# 13_LED_Array.net
KiCad netlist of a schematic drawn in Altium Designer
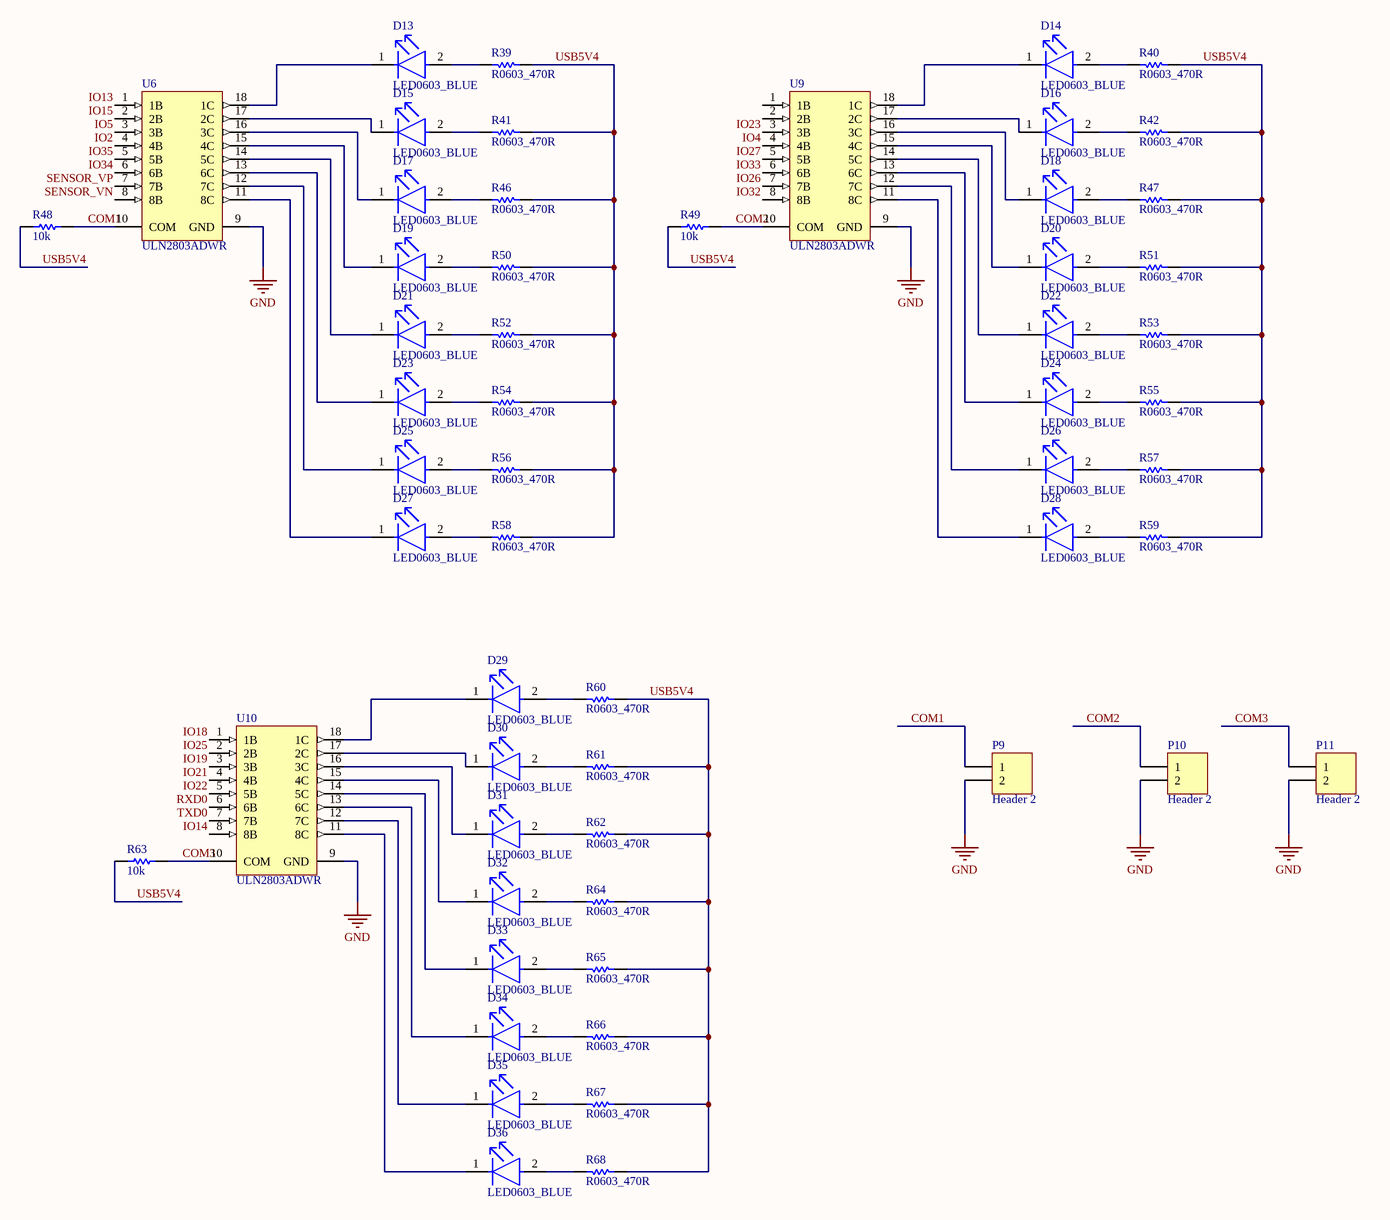
[diagram p0: 13_LED_Array.SchDoc]

(export (version "E")
  (design (tool "Eeschema 10.0.6"))
  (components
    (comp (ref "D13")
      (value "LED0603_BLUE")
      (footprint "FP-LTST-C191TBKT-MFG")
      (description "LED BLUE CLEAR CHIP SMD")
      (libsource (lib "Altium Content Vault") (part "8706943c75ba83719d021d2fdc84c58"))
    )
    (comp (ref "D14")
      (value "LED0603_BLUE")
      (footprint "FP-LTST-C191TBKT-MFG")
      (description "LED BLUE CLEAR CHIP SMD")
      (libsource (lib "Altium Content Vault") (part "8706943c75ba83719d021d2fdc84c58"))
    )
    (comp (ref "D15")
      (value "LED0603_BLUE")
      (footprint "FP-LTST-C191TBKT-MFG")
      (description "LED BLUE CLEAR CHIP SMD")
      (libsource (lib "Altium Content Vault") (part "8706943c75ba83719d021d2fdc84c58"))
    )
    (comp (ref "D16")
      (value "LED0603_BLUE")
      (footprint "FP-LTST-C191TBKT-MFG")
      (description "LED BLUE CLEAR CHIP SMD")
      (libsource (lib "Altium Content Vault") (part "8706943c75ba83719d021d2fdc84c58"))
    )
    (comp (ref "D17")
      (value "LED0603_BLUE")
      (footprint "FP-LTST-C191TBKT-MFG")
      (description "LED BLUE CLEAR CHIP SMD")
      (libsource (lib "Altium Content Vault") (part "8706943c75ba83719d021d2fdc84c58"))
    )
    (comp (ref "D18")
      (value "LED0603_BLUE")
      (footprint "FP-LTST-C191TBKT-MFG")
      (description "LED BLUE CLEAR CHIP SMD")
      (libsource (lib "Altium Content Vault") (part "8706943c75ba83719d021d2fdc84c58"))
    )
    (comp (ref "D19")
      (value "LED0603_BLUE")
      (footprint "FP-LTST-C191TBKT-MFG")
      (description "LED BLUE CLEAR CHIP SMD")
      (libsource (lib "Altium Content Vault") (part "8706943c75ba83719d021d2fdc84c58"))
    )
    (comp (ref "D20")
      (value "LED0603_BLUE")
      (footprint "FP-LTST-C191TBKT-MFG")
      (description "LED BLUE CLEAR CHIP SMD")
      (libsource (lib "Altium Content Vault") (part "8706943c75ba83719d021d2fdc84c58"))
    )
    (comp (ref "D21")
      (value "LED0603_BLUE")
      (footprint "FP-LTST-C191TBKT-MFG")
      (description "LED BLUE CLEAR CHIP SMD")
      (libsource (lib "Altium Content Vault") (part "8706943c75ba83719d021d2fdc84c58"))
    )
    (comp (ref "D22")
      (value "LED0603_BLUE")
      (footprint "FP-LTST-C191TBKT-MFG")
      (description "LED BLUE CLEAR CHIP SMD")
      (libsource (lib "Altium Content Vault") (part "8706943c75ba83719d021d2fdc84c58"))
    )
    (comp (ref "D23")
      (value "LED0603_BLUE")
      (footprint "FP-LTST-C191TBKT-MFG")
      (description "LED BLUE CLEAR CHIP SMD")
      (libsource (lib "Altium Content Vault") (part "8706943c75ba83719d021d2fdc84c58"))
    )
    (comp (ref "D24")
      (value "LED0603_BLUE")
      (footprint "FP-LTST-C191TBKT-MFG")
      (description "LED BLUE CLEAR CHIP SMD")
      (libsource (lib "Altium Content Vault") (part "8706943c75ba83719d021d2fdc84c58"))
    )
    (comp (ref "D25")
      (value "LED0603_BLUE")
      (footprint "FP-LTST-C191TBKT-MFG")
      (description "LED BLUE CLEAR CHIP SMD")
      (libsource (lib "Altium Content Vault") (part "8706943c75ba83719d021d2fdc84c58"))
    )
    (comp (ref "D26")
      (value "LED0603_BLUE")
      (footprint "FP-LTST-C191TBKT-MFG")
      (description "LED BLUE CLEAR CHIP SMD")
      (libsource (lib "Altium Content Vault") (part "8706943c75ba83719d021d2fdc84c58"))
    )
    (comp (ref "D27")
      (value "LED0603_BLUE")
      (footprint "FP-LTST-C191TBKT-MFG")
      (description "LED BLUE CLEAR CHIP SMD")
      (libsource (lib "Altium Content Vault") (part "8706943c75ba83719d021d2fdc84c58"))
    )
    (comp (ref "D28")
      (value "LED0603_BLUE")
      (footprint "FP-LTST-C191TBKT-MFG")
      (description "LED BLUE CLEAR CHIP SMD")
      (libsource (lib "Altium Content Vault") (part "8706943c75ba83719d021d2fdc84c58"))
    )
    (comp (ref "D29")
      (value "LED0603_BLUE")
      (footprint "FP-LTST-C191TBKT-MFG")
      (description "LED BLUE CLEAR CHIP SMD")
      (libsource (lib "Altium Content Vault") (part "8706943c75ba83719d021d2fdc84c58"))
    )
    (comp (ref "D30")
      (value "LED0603_BLUE")
      (footprint "FP-LTST-C191TBKT-MFG")
      (description "LED BLUE CLEAR CHIP SMD")
      (libsource (lib "Altium Content Vault") (part "8706943c75ba83719d021d2fdc84c58"))
    )
    (comp (ref "D31")
      (value "LED0603_BLUE")
      (footprint "FP-LTST-C191TBKT-MFG")
      (description "LED BLUE CLEAR CHIP SMD")
      (libsource (lib "Altium Content Vault") (part "8706943c75ba83719d021d2fdc84c58"))
    )
    (comp (ref "D32")
      (value "LED0603_BLUE")
      (footprint "FP-LTST-C191TBKT-MFG")
      (description "LED BLUE CLEAR CHIP SMD")
      (libsource (lib "Altium Content Vault") (part "8706943c75ba83719d021d2fdc84c58"))
    )
    (comp (ref "D33")
      (value "LED0603_BLUE")
      (footprint "FP-LTST-C191TBKT-MFG")
      (description "LED BLUE CLEAR CHIP SMD")
      (libsource (lib "Altium Content Vault") (part "8706943c75ba83719d021d2fdc84c58"))
    )
    (comp (ref "D34")
      (value "LED0603_BLUE")
      (footprint "FP-LTST-C191TBKT-MFG")
      (description "LED BLUE CLEAR CHIP SMD")
      (libsource (lib "Altium Content Vault") (part "8706943c75ba83719d021d2fdc84c58"))
    )
    (comp (ref "D35")
      (value "LED0603_BLUE")
      (footprint "FP-LTST-C191TBKT-MFG")
      (description "LED BLUE CLEAR CHIP SMD")
      (libsource (lib "Altium Content Vault") (part "8706943c75ba83719d021d2fdc84c58"))
    )
    (comp (ref "D36")
      (value "LED0603_BLUE")
      (footprint "FP-LTST-C191TBKT-MFG")
      (description "LED BLUE CLEAR CHIP SMD")
      (libsource (lib "Altium Content Vault") (part "8706943c75ba83719d021d2fdc84c58"))
    )
    (comp (ref "P9")
      (value "Header 2")
      (footprint "HDR1X2")
      (description "Header, 2-Pin")
      (fields (field (name "PUBLISHER") "Altium Limited"))
      (libsource (lib "Miscellaneous Connectors") (part "Header 2"))
    )
    (comp (ref "P10")
      (value "Header 2")
      (footprint "HDR1X2")
      (description "Header, 2-Pin")
      (fields (field (name "PUBLISHER") "Altium Limited"))
      (libsource (lib "Miscellaneous Connectors") (part "Header 2"))
    )
    (comp (ref "P11")
      (value "Header 2")
      (footprint "HDR1X2")
      (description "Header, 2-Pin")
      (fields (field (name "PUBLISHER") "Altium Limited"))
      (libsource (lib "Miscellaneous Connectors") (part "Header 2"))
    )
    (comp (ref "R39")
      (value "R0603_470R")
      (footprint "RESC1608X55X30NL15T15")
      (fields (field (name "PART NUMBER") "ERJ-3GEYJ471V") (field (name "MANUFACTURER") "Panasonic"))
      (libsource (lib "Altium Content Vault") (part "RES"))
    )
    (comp (ref "R40")
      (value "R0603_470R")
      (footprint "RESC1608X55X30NL15T15")
      (fields (field (name "PART NUMBER") "ERJ-3GEYJ471V") (field (name "MANUFACTURER") "Panasonic"))
      (libsource (lib "Altium Content Vault") (part "RES"))
    )
    (comp (ref "R41")
      (value "R0603_470R")
      (footprint "RESC1608X55X30NL15T15")
      (fields (field (name "PART NUMBER") "ERJ-3GEYJ471V") (field (name "MANUFACTURER") "Panasonic"))
      (libsource (lib "Altium Content Vault") (part "RES"))
    )
    (comp (ref "R42")
      (value "R0603_470R")
      (footprint "RESC1608X55X30NL15T15")
      (fields (field (name "PART NUMBER") "ERJ-3GEYJ471V") (field (name "MANUFACTURER") "Panasonic"))
      (libsource (lib "Altium Content Vault") (part "RES"))
    )
    (comp (ref "R46")
      (value "R0603_470R")
      (footprint "RESC1608X55X30NL15T15")
      (fields (field (name "PART NUMBER") "ERJ-3GEYJ471V") (field (name "MANUFACTURER") "Panasonic"))
      (libsource (lib "Altium Content Vault") (part "RES"))
    )
    (comp (ref "R47")
      (value "R0603_470R")
      (footprint "RESC1608X55X30NL15T15")
      (fields (field (name "PART NUMBER") "ERJ-3GEYJ471V") (field (name "MANUFACTURER") "Panasonic"))
      (libsource (lib "Altium Content Vault") (part "RES"))
    )
    (comp (ref "R48")
      (value "10k")
      (footprint "RESC1609X55X30LL15T15")
      (description "Chip Resistor, 10 KOhm, +/- 1%, 0.1 W, -55 to 155 degC, 0603 (1608 Metric), RoHS, Tape and Reel")
      (fields (field (name "TOLERANCE") "1%") (field (name "MANUFACTURER") "Panasonic"))
      (libsource (lib "Altium Content Vault") (part "RES-2"))
    )
    (comp (ref "R49")
      (value "10k")
      (footprint "RESC1609X55X30LL15T15")
      (description "Chip Resistor, 10 KOhm, +/- 1%, 0.1 W, -55 to 155 degC, 0603 (1608 Metric), RoHS, Tape and Reel")
      (fields (field (name "TOLERANCE") "1%") (field (name "MANUFACTURER") "Panasonic"))
      (libsource (lib "Altium Content Vault") (part "RES-2"))
    )
    (comp (ref "R50")
      (value "R0603_470R")
      (footprint "RESC1608X55X30NL15T15")
      (fields (field (name "PART NUMBER") "ERJ-3GEYJ471V") (field (name "MANUFACTURER") "Panasonic"))
      (libsource (lib "Altium Content Vault") (part "RES"))
    )
    (comp (ref "R51")
      (value "R0603_470R")
      (footprint "RESC1608X55X30NL15T15")
      (fields (field (name "PART NUMBER") "ERJ-3GEYJ471V") (field (name "MANUFACTURER") "Panasonic"))
      (libsource (lib "Altium Content Vault") (part "RES"))
    )
    (comp (ref "R52")
      (value "R0603_470R")
      (footprint "RESC1608X55X30NL15T15")
      (fields (field (name "PART NUMBER") "ERJ-3GEYJ471V") (field (name "MANUFACTURER") "Panasonic"))
      (libsource (lib "Altium Content Vault") (part "RES"))
    )
    (comp (ref "R53")
      (value "R0603_470R")
      (footprint "RESC1608X55X30NL15T15")
      (fields (field (name "PART NUMBER") "ERJ-3GEYJ471V") (field (name "MANUFACTURER") "Panasonic"))
      (libsource (lib "Altium Content Vault") (part "RES"))
    )
    (comp (ref "R54")
      (value "R0603_470R")
      (footprint "RESC1608X55X30NL15T15")
      (fields (field (name "PART NUMBER") "ERJ-3GEYJ471V") (field (name "MANUFACTURER") "Panasonic"))
      (libsource (lib "Altium Content Vault") (part "RES"))
    )
    (comp (ref "R55")
      (value "R0603_470R")
      (footprint "RESC1608X55X30NL15T15")
      (fields (field (name "PART NUMBER") "ERJ-3GEYJ471V") (field (name "MANUFACTURER") "Panasonic"))
      (libsource (lib "Altium Content Vault") (part "RES"))
    )
    (comp (ref "R56")
      (value "R0603_470R")
      (footprint "RESC1608X55X30NL15T15")
      (fields (field (name "PART NUMBER") "ERJ-3GEYJ471V") (field (name "MANUFACTURER") "Panasonic"))
      (libsource (lib "Altium Content Vault") (part "RES"))
    )
    (comp (ref "R57")
      (value "R0603_470R")
      (footprint "RESC1608X55X30NL15T15")
      (fields (field (name "PART NUMBER") "ERJ-3GEYJ471V") (field (name "MANUFACTURER") "Panasonic"))
      (libsource (lib "Altium Content Vault") (part "RES"))
    )
    (comp (ref "R58")
      (value "R0603_470R")
      (footprint "RESC1608X55X30NL15T15")
      (fields (field (name "PART NUMBER") "ERJ-3GEYJ471V") (field (name "MANUFACTURER") "Panasonic"))
      (libsource (lib "Altium Content Vault") (part "RES"))
    )
    (comp (ref "R59")
      (value "R0603_470R")
      (footprint "RESC1608X55X30NL15T15")
      (fields (field (name "PART NUMBER") "ERJ-3GEYJ471V") (field (name "MANUFACTURER") "Panasonic"))
      (libsource (lib "Altium Content Vault") (part "RES"))
    )
    (comp (ref "R60")
      (value "R0603_470R")
      (footprint "RESC1608X55X30NL15T15")
      (fields (field (name "PART NUMBER") "ERJ-3GEYJ471V") (field (name "MANUFACTURER") "Panasonic"))
      (libsource (lib "Altium Content Vault") (part "RES"))
    )
    (comp (ref "R61")
      (value "R0603_470R")
      (footprint "RESC1608X55X30NL15T15")
      (fields (field (name "PART NUMBER") "ERJ-3GEYJ471V") (field (name "MANUFACTURER") "Panasonic"))
      (libsource (lib "Altium Content Vault") (part "RES"))
    )
    (comp (ref "R62")
      (value "R0603_470R")
      (footprint "RESC1608X55X30NL15T15")
      (fields (field (name "PART NUMBER") "ERJ-3GEYJ471V") (field (name "MANUFACTURER") "Panasonic"))
      (libsource (lib "Altium Content Vault") (part "RES"))
    )
    (comp (ref "R63")
      (value "10k")
      (footprint "RESC1609X55X30LL15T15")
      (description "Chip Resistor, 10 KOhm, +/- 1%, 0.1 W, -55 to 155 degC, 0603 (1608 Metric), RoHS, Tape and Reel")
      (fields (field (name "TOLERANCE") "1%") (field (name "MANUFACTURER") "Panasonic"))
      (libsource (lib "Altium Content Vault") (part "RES-2"))
    )
    (comp (ref "R64")
      (value "R0603_470R")
      (footprint "RESC1608X55X30NL15T15")
      (fields (field (name "PART NUMBER") "ERJ-3GEYJ471V") (field (name "MANUFACTURER") "Panasonic"))
      (libsource (lib "Altium Content Vault") (part "RES"))
    )
    (comp (ref "R65")
      (value "R0603_470R")
      (footprint "RESC1608X55X30NL15T15")
      (fields (field (name "PART NUMBER") "ERJ-3GEYJ471V") (field (name "MANUFACTURER") "Panasonic"))
      (libsource (lib "Altium Content Vault") (part "RES"))
    )
    (comp (ref "R66")
      (value "R0603_470R")
      (footprint "RESC1608X55X30NL15T15")
      (fields (field (name "PART NUMBER") "ERJ-3GEYJ471V") (field (name "MANUFACTURER") "Panasonic"))
      (libsource (lib "Altium Content Vault") (part "RES"))
    )
    (comp (ref "R67")
      (value "R0603_470R")
      (footprint "RESC1608X55X30NL15T15")
      (fields (field (name "PART NUMBER") "ERJ-3GEYJ471V") (field (name "MANUFACTURER") "Panasonic"))
      (libsource (lib "Altium Content Vault") (part "RES"))
    )
    (comp (ref "R68")
      (value "R0603_470R")
      (footprint "RESC1608X55X30NL15T15")
      (fields (field (name "PART NUMBER") "ERJ-3GEYJ471V") (field (name "MANUFACTURER") "Panasonic"))
      (libsource (lib "Altium Content Vault") (part "RES"))
    )
    (comp (ref "U6")
      (value "ULN2803ADWR")
      (footprint "DW0018A_L")
      (fields (field (name "MANUFACTURER") "Texas Instruments") (field (name "PARTNUMBER") "ULN2803A"))
      (libsource (lib "Altium Content Vault") (part "TI-ULN2803A-SOIC_DW-18"))
    )
    (comp (ref "U9")
      (value "ULN2803ADWR")
      (footprint "DW0018A_L")
      (fields (field (name "MANUFACTURER") "Texas Instruments") (field (name "PARTNUMBER") "ULN2803A"))
      (libsource (lib "Altium Content Vault") (part "TI-ULN2803A-SOIC_DW-18"))
    )
    (comp (ref "U10")
      (value "ULN2803ADWR")
      (footprint "DW0018A_L")
      (fields (field (name "MANUFACTURER") "Texas Instruments") (field (name "PARTNUMBER") "ULN2803A"))
      (libsource (lib "Altium Content Vault") (part "TI-ULN2803A-SOIC_DW-18"))
    )
  )
  (nets
    (net (code "1") (name "/COM1") (class "Default")
      (node (ref "P9") (pin "1") (pinfunction "1_1") (pintype "passive"))
      (node (ref "R48") (pin "2") (pinfunction "2_2") (pintype "passive"))
      (node (ref "U6") (pin "10") (pinfunction "COM_10") (pintype "passive"))
    )
    (net (code "2") (name "/COM2") (class "Default")
      (node (ref "P10") (pin "1") (pinfunction "1_1") (pintype "passive"))
      (node (ref "R49") (pin "2") (pinfunction "2_2") (pintype "passive"))
      (node (ref "U9") (pin "10") (pinfunction "COM_10") (pintype "passive"))
    )
    (net (code "3") (name "/COM3") (class "Default")
      (node (ref "P11") (pin "1") (pinfunction "1_1") (pintype "passive"))
      (node (ref "R63") (pin "2") (pinfunction "2_2") (pintype "passive"))
      (node (ref "U10") (pin "10") (pinfunction "COM_10") (pintype "passive"))
    )
    (net (code "4") (name "/IO2") (class "Default")
      (node (ref "U6") (pin "4") (pinfunction "4B_4") (pintype "input"))
    )
    (net (code "5") (name "/IO4") (class "Default")
      (node (ref "U9") (pin "4") (pinfunction "4B_4") (pintype "input"))
    )
    (net (code "6") (name "/IO5") (class "Default")
      (node (ref "U6") (pin "3") (pinfunction "3B_3") (pintype "input"))
    )
    (net (code "7") (name "/IO13") (class "Default")
      (node (ref "U6") (pin "1") (pinfunction "1B_1") (pintype "input"))
    )
    (net (code "8") (name "/IO14") (class "Default")
      (node (ref "U10") (pin "8") (pinfunction "8B_8") (pintype "input"))
    )
    (net (code "9") (name "/IO15") (class "Default")
      (node (ref "U6") (pin "2") (pinfunction "2B_2") (pintype "input"))
    )
    (net (code "10") (name "/IO18") (class "Default")
      (node (ref "U10") (pin "1") (pinfunction "1B_1") (pintype "input"))
    )
    (net (code "11") (name "/IO19") (class "Default")
      (node (ref "U10") (pin "3") (pinfunction "3B_3") (pintype "input"))
    )
    (net (code "12") (name "/IO21") (class "Default")
      (node (ref "U10") (pin "4") (pinfunction "4B_4") (pintype "input"))
    )
    (net (code "13") (name "/IO22") (class "Default")
      (node (ref "U10") (pin "5") (pinfunction "5B_5") (pintype "input"))
    )
    (net (code "14") (name "/IO23") (class "Default")
      (node (ref "U9") (pin "3") (pinfunction "3B_3") (pintype "input"))
    )
    (net (code "15") (name "/IO25") (class "Default")
      (node (ref "U10") (pin "2") (pinfunction "2B_2") (pintype "input"))
    )
    (net (code "16") (name "/IO26") (class "Default")
      (node (ref "U9") (pin "7") (pinfunction "7B_7") (pintype "input"))
    )
    (net (code "17") (name "/IO27") (class "Default")
      (node (ref "U9") (pin "5") (pinfunction "5B_5") (pintype "input"))
    )
    (net (code "18") (name "/IO32") (class "Default")
      (node (ref "U9") (pin "8") (pinfunction "8B_8") (pintype "input"))
    )
    (net (code "19") (name "/IO33") (class "Default")
      (node (ref "U9") (pin "6") (pinfunction "6B_6") (pintype "input"))
    )
    (net (code "20") (name "/IO34") (class "Default")
      (node (ref "U6") (pin "6") (pinfunction "6B_6") (pintype "input"))
    )
    (net (code "21") (name "/IO35") (class "Default")
      (node (ref "U6") (pin "5") (pinfunction "5B_5") (pintype "input"))
    )
    (net (code "22") (name "/RXD0") (class "Default")
      (node (ref "U10") (pin "6") (pinfunction "6B_6") (pintype "input"))
    )
    (net (code "23") (name "/SENSOR_VN") (class "Default")
      (node (ref "U6") (pin "8") (pinfunction "8B_8") (pintype "input"))
    )
    (net (code "24") (name "/SENSOR_VP") (class "Default")
      (node (ref "U6") (pin "7") (pinfunction "7B_7") (pintype "input"))
    )
    (net (code "25") (name "/TXD0") (class "Default")
      (node (ref "U10") (pin "7") (pinfunction "7B_7") (pintype "input"))
    )
    (net (code "26") (name "/USB5V4") (class "Default")
      (node (ref "R39") (pin "1") (pinfunction "1_1") (pintype "passive"))
      (node (ref "R40") (pin "1") (pinfunction "1_1") (pintype "passive"))
      (node (ref "R41") (pin "1") (pinfunction "1_1") (pintype "passive"))
      (node (ref "R42") (pin "1") (pinfunction "1_1") (pintype "passive"))
      (node (ref "R46") (pin "1") (pinfunction "1_1") (pintype "passive"))
      (node (ref "R47") (pin "1") (pinfunction "1_1") (pintype "passive"))
      (node (ref "R48") (pin "1") (pinfunction "1_1") (pintype "passive"))
      (node (ref "R49") (pin "1") (pinfunction "1_1") (pintype "passive"))
      (node (ref "R50") (pin "1") (pinfunction "1_1") (pintype "passive"))
      (node (ref "R51") (pin "1") (pinfunction "1_1") (pintype "passive"))
      (node (ref "R52") (pin "1") (pinfunction "1_1") (pintype "passive"))
      (node (ref "R53") (pin "1") (pinfunction "1_1") (pintype "passive"))
      (node (ref "R54") (pin "1") (pinfunction "1_1") (pintype "passive"))
      (node (ref "R55") (pin "1") (pinfunction "1_1") (pintype "passive"))
      (node (ref "R56") (pin "1") (pinfunction "1_1") (pintype "passive"))
      (node (ref "R57") (pin "1") (pinfunction "1_1") (pintype "passive"))
      (node (ref "R58") (pin "1") (pinfunction "1_1") (pintype "passive"))
      (node (ref "R59") (pin "1") (pinfunction "1_1") (pintype "passive"))
      (node (ref "R60") (pin "1") (pinfunction "1_1") (pintype "passive"))
      (node (ref "R61") (pin "1") (pinfunction "1_1") (pintype "passive"))
      (node (ref "R62") (pin "1") (pinfunction "1_1") (pintype "passive"))
      (node (ref "R63") (pin "1") (pinfunction "1_1") (pintype "passive"))
      (node (ref "R64") (pin "1") (pinfunction "1_1") (pintype "passive"))
      (node (ref "R65") (pin "1") (pinfunction "1_1") (pintype "passive"))
      (node (ref "R66") (pin "1") (pinfunction "1_1") (pintype "passive"))
      (node (ref "R67") (pin "1") (pinfunction "1_1") (pintype "passive"))
      (node (ref "R68") (pin "1") (pinfunction "1_1") (pintype "passive"))
    )
    (net (code "27") (name "GND") (class "Default")
      (node (ref "P10") (pin "2") (pinfunction "2_2") (pintype "passive"))
      (node (ref "P11") (pin "2") (pinfunction "2_2") (pintype "passive"))
      (node (ref "P9") (pin "2") (pinfunction "2_2") (pintype "passive"))
      (node (ref "U10") (pin "9") (pinfunction "GND_9") (pintype "power_in"))
      (node (ref "U6") (pin "9") (pinfunction "GND_9") (pintype "power_in"))
      (node (ref "U9") (pin "9") (pinfunction "GND_9") (pintype "power_in"))
    )
    (net (code "28") (name "Net-(D13-A)") (class "Default")
      (node (ref "D13") (pin "2") (pinfunction "A_2") (pintype "passive"))
      (node (ref "R39") (pin "2") (pinfunction "2_2") (pintype "passive"))
    )
    (net (code "29") (name "Net-(D13-C)") (class "Default")
      (node (ref "D13") (pin "1") (pinfunction "C_1") (pintype "passive"))
      (node (ref "U6") (pin "18") (pinfunction "1C_18") (pintype "output"))
    )
    (net (code "30") (name "Net-(D14-A)") (class "Default")
      (node (ref "D14") (pin "2") (pinfunction "A_2") (pintype "passive"))
      (node (ref "R40") (pin "2") (pinfunction "2_2") (pintype "passive"))
    )
    (net (code "31") (name "Net-(D14-C)") (class "Default")
      (node (ref "D14") (pin "1") (pinfunction "C_1") (pintype "passive"))
      (node (ref "U9") (pin "18") (pinfunction "1C_18") (pintype "output"))
    )
    (net (code "32") (name "Net-(D15-A)") (class "Default")
      (node (ref "D15") (pin "2") (pinfunction "A_2") (pintype "passive"))
      (node (ref "R41") (pin "2") (pinfunction "2_2") (pintype "passive"))
    )
    (net (code "33") (name "Net-(D15-C)") (class "Default")
      (node (ref "D15") (pin "1") (pinfunction "C_1") (pintype "passive"))
      (node (ref "U6") (pin "17") (pinfunction "2C_17") (pintype "output"))
    )
    (net (code "34") (name "Net-(D16-A)") (class "Default")
      (node (ref "D16") (pin "2") (pinfunction "A_2") (pintype "passive"))
      (node (ref "R42") (pin "2") (pinfunction "2_2") (pintype "passive"))
    )
    (net (code "35") (name "Net-(D16-C)") (class "Default")
      (node (ref "D16") (pin "1") (pinfunction "C_1") (pintype "passive"))
      (node (ref "U9") (pin "17") (pinfunction "2C_17") (pintype "output"))
    )
    (net (code "36") (name "Net-(D17-A)") (class "Default")
      (node (ref "D17") (pin "2") (pinfunction "A_2") (pintype "passive"))
      (node (ref "R46") (pin "2") (pinfunction "2_2") (pintype "passive"))
    )
    (net (code "37") (name "Net-(D17-C)") (class "Default")
      (node (ref "D17") (pin "1") (pinfunction "C_1") (pintype "passive"))
      (node (ref "U6") (pin "16") (pinfunction "3C_16") (pintype "output"))
    )
    (net (code "38") (name "Net-(D18-A)") (class "Default")
      (node (ref "D18") (pin "2") (pinfunction "A_2") (pintype "passive"))
      (node (ref "R47") (pin "2") (pinfunction "2_2") (pintype "passive"))
    )
    (net (code "39") (name "Net-(D18-C)") (class "Default")
      (node (ref "D18") (pin "1") (pinfunction "C_1") (pintype "passive"))
      (node (ref "U9") (pin "16") (pinfunction "3C_16") (pintype "output"))
    )
    (net (code "40") (name "Net-(D19-A)") (class "Default")
      (node (ref "D19") (pin "2") (pinfunction "A_2") (pintype "passive"))
      (node (ref "R50") (pin "2") (pinfunction "2_2") (pintype "passive"))
    )
    (net (code "41") (name "Net-(D19-C)") (class "Default")
      (node (ref "D19") (pin "1") (pinfunction "C_1") (pintype "passive"))
      (node (ref "U6") (pin "15") (pinfunction "4C_15") (pintype "output"))
    )
    (net (code "42") (name "Net-(D20-A)") (class "Default")
      (node (ref "D20") (pin "2") (pinfunction "A_2") (pintype "passive"))
      (node (ref "R51") (pin "2") (pinfunction "2_2") (pintype "passive"))
    )
    (net (code "43") (name "Net-(D20-C)") (class "Default")
      (node (ref "D20") (pin "1") (pinfunction "C_1") (pintype "passive"))
      (node (ref "U9") (pin "15") (pinfunction "4C_15") (pintype "output"))
    )
    (net (code "44") (name "Net-(D21-A)") (class "Default")
      (node (ref "D21") (pin "2") (pinfunction "A_2") (pintype "passive"))
      (node (ref "R52") (pin "2") (pinfunction "2_2") (pintype "passive"))
    )
    (net (code "45") (name "Net-(D21-C)") (class "Default")
      (node (ref "D21") (pin "1") (pinfunction "C_1") (pintype "passive"))
      (node (ref "U6") (pin "14") (pinfunction "5C_14") (pintype "output"))
    )
    (net (code "46") (name "Net-(D22-A)") (class "Default")
      (node (ref "D22") (pin "2") (pinfunction "A_2") (pintype "passive"))
      (node (ref "R53") (pin "2") (pinfunction "2_2") (pintype "passive"))
    )
    (net (code "47") (name "Net-(D22-C)") (class "Default")
      (node (ref "D22") (pin "1") (pinfunction "C_1") (pintype "passive"))
      (node (ref "U9") (pin "14") (pinfunction "5C_14") (pintype "output"))
    )
    (net (code "48") (name "Net-(D23-A)") (class "Default")
      (node (ref "D23") (pin "2") (pinfunction "A_2") (pintype "passive"))
      (node (ref "R54") (pin "2") (pinfunction "2_2") (pintype "passive"))
    )
    (net (code "49") (name "Net-(D23-C)") (class "Default")
      (node (ref "D23") (pin "1") (pinfunction "C_1") (pintype "passive"))
      (node (ref "U6") (pin "13") (pinfunction "6C_13") (pintype "output"))
    )
    (net (code "50") (name "Net-(D24-A)") (class "Default")
      (node (ref "D24") (pin "2") (pinfunction "A_2") (pintype "passive"))
      (node (ref "R55") (pin "2") (pinfunction "2_2") (pintype "passive"))
    )
    (net (code "51") (name "Net-(D24-C)") (class "Default")
      (node (ref "D24") (pin "1") (pinfunction "C_1") (pintype "passive"))
      (node (ref "U9") (pin "13") (pinfunction "6C_13") (pintype "output"))
    )
    (net (code "52") (name "Net-(D25-A)") (class "Default")
      (node (ref "D25") (pin "2") (pinfunction "A_2") (pintype "passive"))
      (node (ref "R56") (pin "2") (pinfunction "2_2") (pintype "passive"))
    )
    (net (code "53") (name "Net-(D25-C)") (class "Default")
      (node (ref "D25") (pin "1") (pinfunction "C_1") (pintype "passive"))
      (node (ref "U6") (pin "12") (pinfunction "7C_12") (pintype "output"))
    )
    (net (code "54") (name "Net-(D26-A)") (class "Default")
      (node (ref "D26") (pin "2") (pinfunction "A_2") (pintype "passive"))
      (node (ref "R57") (pin "2") (pinfunction "2_2") (pintype "passive"))
    )
    (net (code "55") (name "Net-(D26-C)") (class "Default")
      (node (ref "D26") (pin "1") (pinfunction "C_1") (pintype "passive"))
      (node (ref "U9") (pin "12") (pinfunction "7C_12") (pintype "output"))
    )
    (net (code "56") (name "Net-(D27-A)") (class "Default")
      (node (ref "D27") (pin "2") (pinfunction "A_2") (pintype "passive"))
      (node (ref "R58") (pin "2") (pinfunction "2_2") (pintype "passive"))
    )
    (net (code "57") (name "Net-(D27-C)") (class "Default")
      (node (ref "D27") (pin "1") (pinfunction "C_1") (pintype "passive"))
      (node (ref "U6") (pin "11") (pinfunction "8C_11") (pintype "output"))
    )
    (net (code "58") (name "Net-(D28-A)") (class "Default")
      (node (ref "D28") (pin "2") (pinfunction "A_2") (pintype "passive"))
      (node (ref "R59") (pin "2") (pinfunction "2_2") (pintype "passive"))
    )
    (net (code "59") (name "Net-(D28-C)") (class "Default")
      (node (ref "D28") (pin "1") (pinfunction "C_1") (pintype "passive"))
      (node (ref "U9") (pin "11") (pinfunction "8C_11") (pintype "output"))
    )
    (net (code "60") (name "Net-(D29-A)") (class "Default")
      (node (ref "D29") (pin "2") (pinfunction "A_2") (pintype "passive"))
      (node (ref "R60") (pin "2") (pinfunction "2_2") (pintype "passive"))
    )
    (net (code "61") (name "Net-(D29-C)") (class "Default")
      (node (ref "D29") (pin "1") (pinfunction "C_1") (pintype "passive"))
      (node (ref "U10") (pin "18") (pinfunction "1C_18") (pintype "output"))
    )
    (net (code "62") (name "Net-(D30-A)") (class "Default")
      (node (ref "D30") (pin "2") (pinfunction "A_2") (pintype "passive"))
      (node (ref "R61") (pin "2") (pinfunction "2_2") (pintype "passive"))
    )
    (net (code "63") (name "Net-(D30-C)") (class "Default")
      (node (ref "D30") (pin "1") (pinfunction "C_1") (pintype "passive"))
      (node (ref "U10") (pin "17") (pinfunction "2C_17") (pintype "output"))
    )
    (net (code "64") (name "Net-(D31-A)") (class "Default")
      (node (ref "D31") (pin "2") (pinfunction "A_2") (pintype "passive"))
      (node (ref "R62") (pin "2") (pinfunction "2_2") (pintype "passive"))
    )
    (net (code "65") (name "Net-(D31-C)") (class "Default")
      (node (ref "D31") (pin "1") (pinfunction "C_1") (pintype "passive"))
      (node (ref "U10") (pin "16") (pinfunction "3C_16") (pintype "output"))
    )
    (net (code "66") (name "Net-(D32-A)") (class "Default")
      (node (ref "D32") (pin "2") (pinfunction "A_2") (pintype "passive"))
      (node (ref "R64") (pin "2") (pinfunction "2_2") (pintype "passive"))
    )
    (net (code "67") (name "Net-(D32-C)") (class "Default")
      (node (ref "D32") (pin "1") (pinfunction "C_1") (pintype "passive"))
      (node (ref "U10") (pin "15") (pinfunction "4C_15") (pintype "output"))
    )
    (net (code "68") (name "Net-(D33-A)") (class "Default")
      (node (ref "D33") (pin "2") (pinfunction "A_2") (pintype "passive"))
      (node (ref "R65") (pin "2") (pinfunction "2_2") (pintype "passive"))
    )
    (net (code "69") (name "Net-(D33-C)") (class "Default")
      (node (ref "D33") (pin "1") (pinfunction "C_1") (pintype "passive"))
      (node (ref "U10") (pin "14") (pinfunction "5C_14") (pintype "output"))
    )
    (net (code "70") (name "Net-(D34-A)") (class "Default")
      (node (ref "D34") (pin "2") (pinfunction "A_2") (pintype "passive"))
      (node (ref "R66") (pin "2") (pinfunction "2_2") (pintype "passive"))
    )
    (net (code "71") (name "Net-(D34-C)") (class "Default")
      (node (ref "D34") (pin "1") (pinfunction "C_1") (pintype "passive"))
      (node (ref "U10") (pin "13") (pinfunction "6C_13") (pintype "output"))
    )
    (net (code "72") (name "Net-(D35-A)") (class "Default")
      (node (ref "D35") (pin "2") (pinfunction "A_2") (pintype "passive"))
      (node (ref "R67") (pin "2") (pinfunction "2_2") (pintype "passive"))
    )
    (net (code "73") (name "Net-(D35-C)") (class "Default")
      (node (ref "D35") (pin "1") (pinfunction "C_1") (pintype "passive"))
      (node (ref "U10") (pin "12") (pinfunction "7C_12") (pintype "output"))
    )
    (net (code "74") (name "Net-(D36-A)") (class "Default")
      (node (ref "D36") (pin "2") (pinfunction "A_2") (pintype "passive"))
      (node (ref "R68") (pin "2") (pinfunction "2_2") (pintype "passive"))
    )
    (net (code "75") (name "Net-(D36-C)") (class "Default")
      (node (ref "D36") (pin "1") (pinfunction "C_1") (pintype "passive"))
      (node (ref "U10") (pin "11") (pinfunction "8C_11") (pintype "output"))
    )
    (net (code "76") (name "unconnected-(U9-1B-Pad1)") (class "Default")
      (node (ref "U9") (pin "1") (pinfunction "1B_1") (pintype "input"))
    )
    (net (code "77") (name "unconnected-(U9-2B-Pad2)") (class "Default")
      (node (ref "U9") (pin "2") (pinfunction "2B_2") (pintype "input"))
    )
  )
)
